# Receiver_schematic.net
KiCad netlist of a schematic drawn in EasyEDA
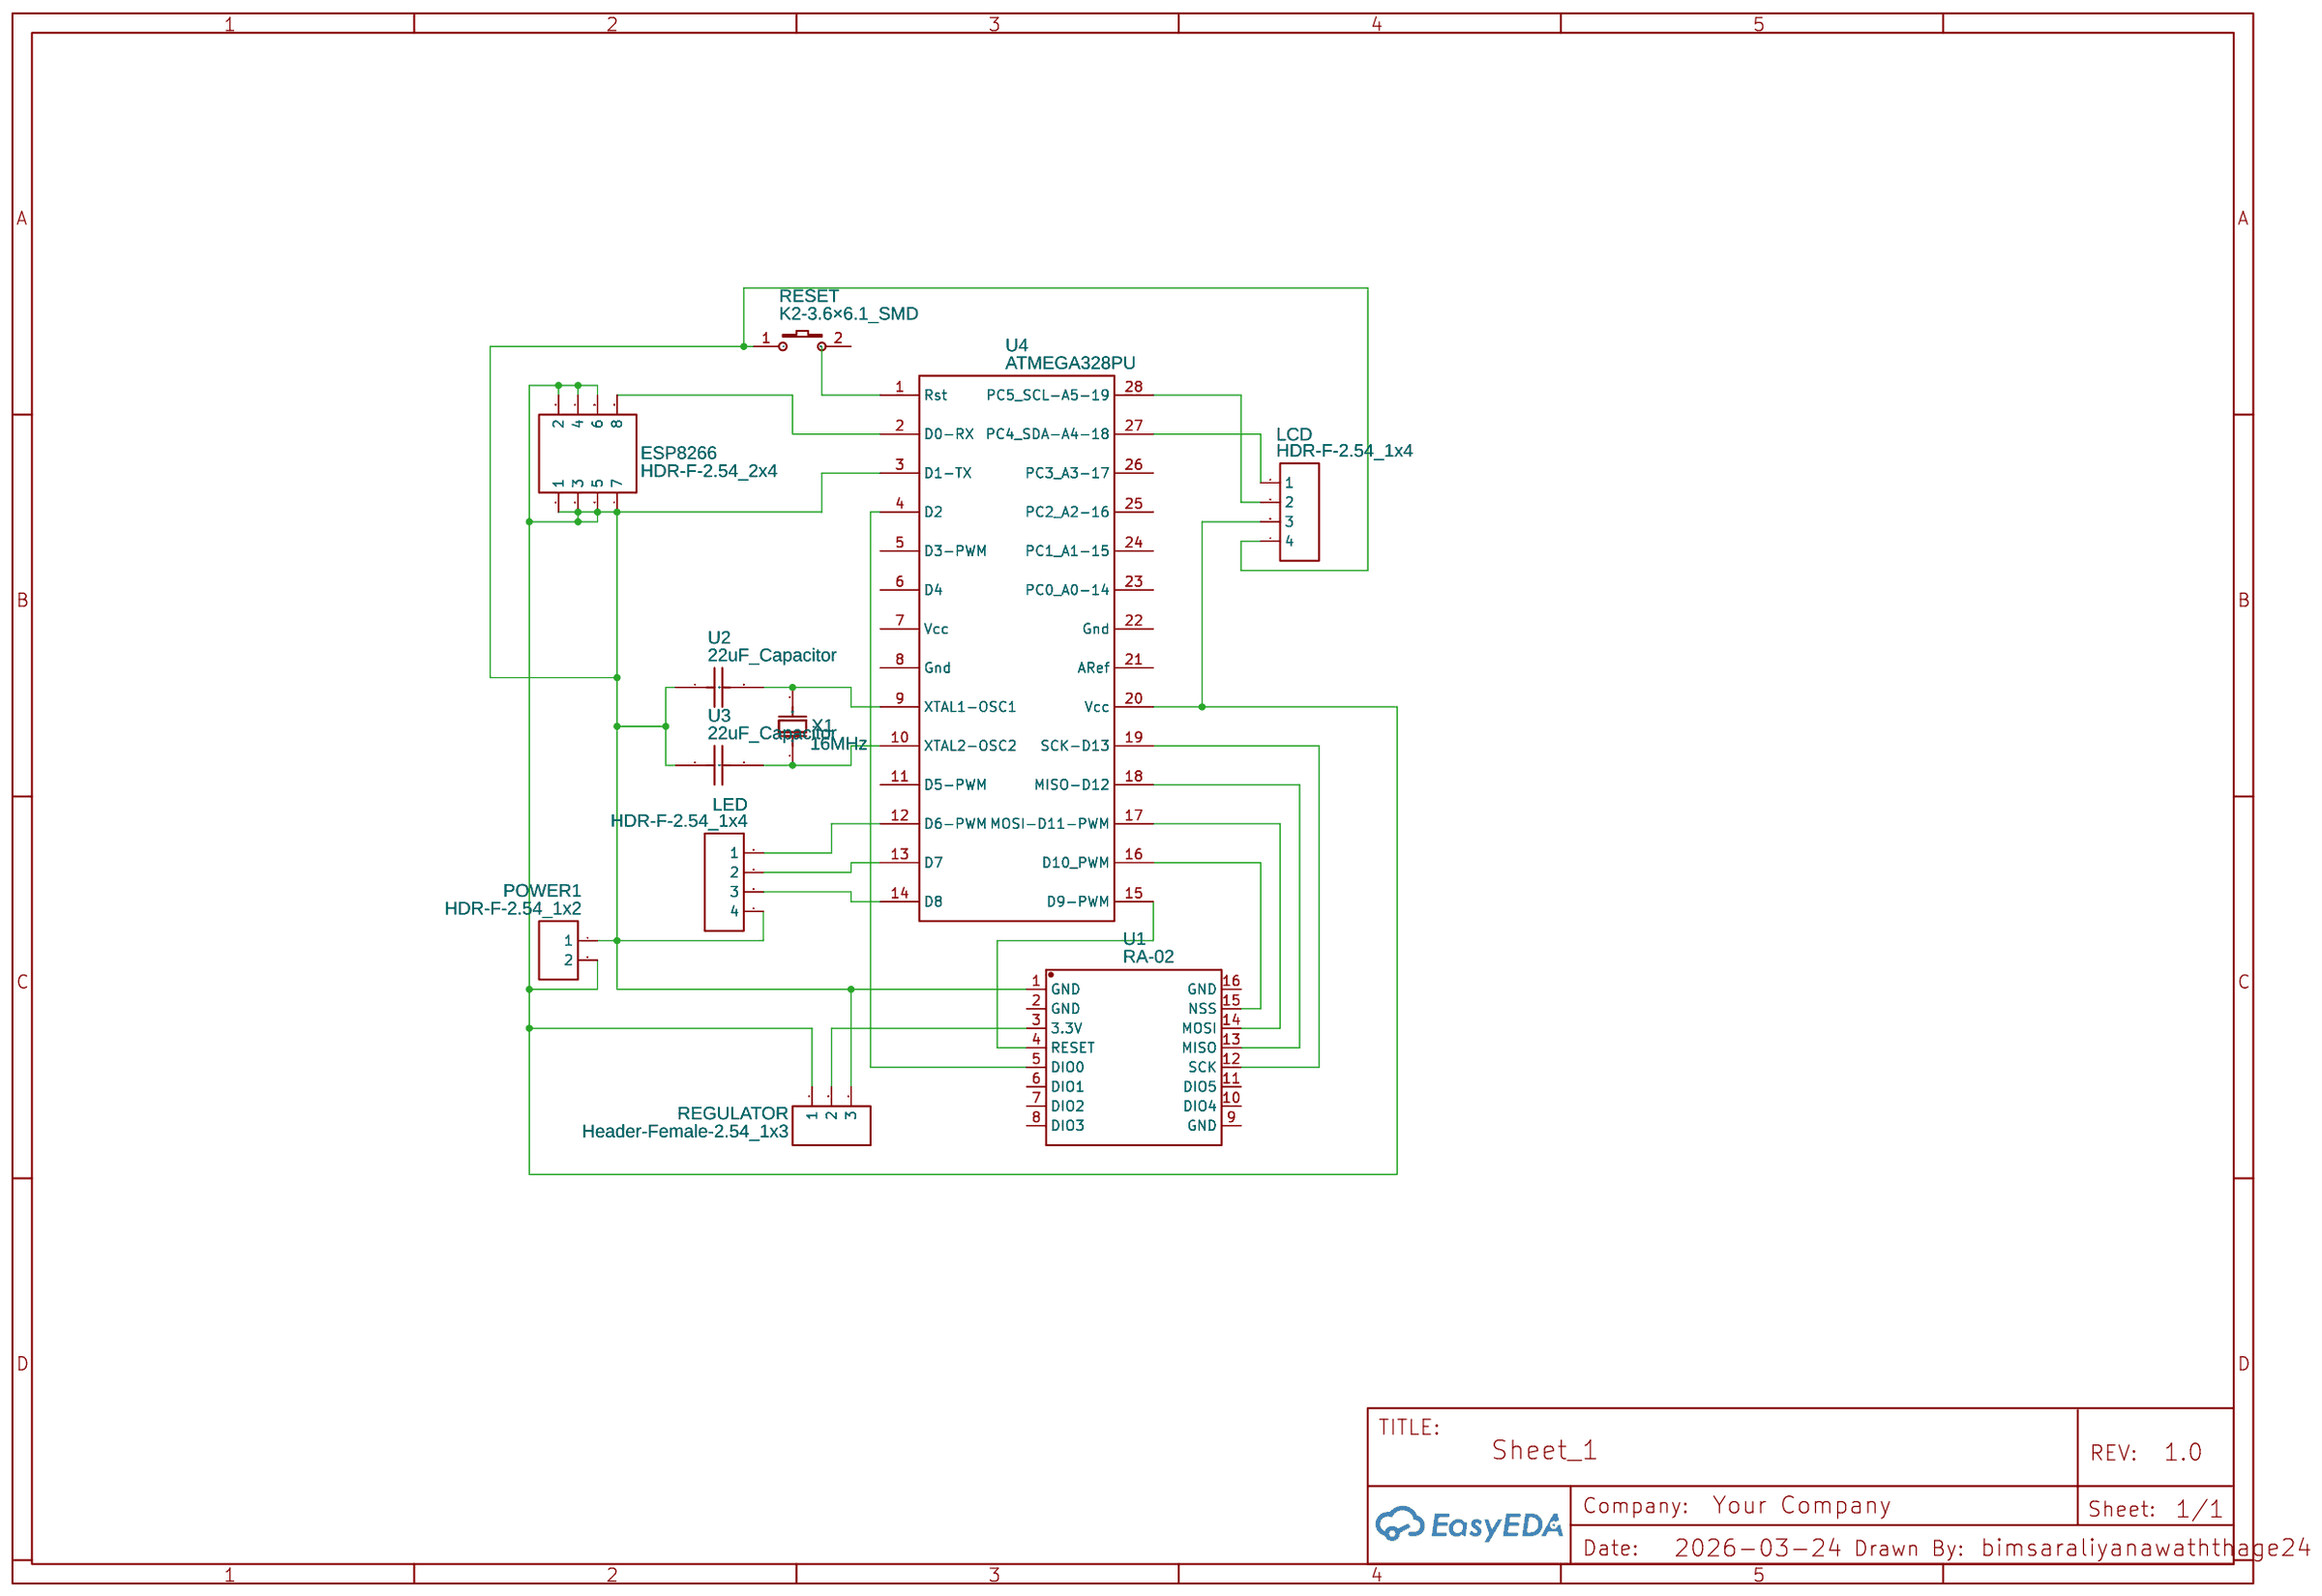
[diagram p0: schematic sheet]

(export (version "E")
  (design (tool "Eeschema 10.0.6"))
  (components
    (comp (ref "ESP8266") (value "HDR-F-2.54_2x4") (libsource (lib "") (part "HDR-F-2.54_2x4")))
    (comp (ref "LCD") (value "HDR-F-2.54_1x4") (libsource (lib "") (part "HDR-F-2.54_1x4_1")))
    (comp (ref "LED") (value "HDR-F-2.54_1x4") (libsource (lib "") (part "HDR-F-2.54_1x4")))
    (comp (ref "POWER1") (value "HDR-F-2.54_1x2") (libsource (lib "") (part "HDR-F-2.54_1x2")))
    (comp (ref "REGULATOR")
      (value "Header-Female-2.54_1x3")
      (fields (field (name "Manufacturer Part") "2.54-1*3P母") (field (name "Manufacturer") "BOOMELE(博穆精密)"))
      (libsource (lib "") (part "Header-Female-2.54_1x3"))
    )
    (comp (ref "RESET")
      (value "K2-3.6×6.1_SMD")
      (fields (field (name "Manufacturer Part") "K2-1107ST-A4SW-06"))
      (libsource (lib "") (part "K2-3.6×6.1_SMD"))
    )
    (comp (ref "U1")
      (value "RA-02")
      (fields (field (name "Manufacturer Part") "Ra-02") (field (name "Manufacturer") "Ai-Thinker(安信可)"))
      (libsource (lib "") (part "RA-02"))
    )
    (comp (ref "U2") (value "22uF_Capacitor") (libsource (lib "") (part "22uF_Capacitor")))
    (comp (ref "U3") (value "22uF_Capacitor") (libsource (lib "") (part "22uF_Capacitor")))
    (comp (ref "U4") (value "ATMEGA328PU") (libsource (lib "") (part "ATMEGA328PU")))
    (comp (ref "X1")
      (value "16MHz")
      (fields (field (name "Manufacturer Part") "9B-48.000MAAE-B") (field (name "Manufacturer") "TXC"))
      (libsource (lib "") (part "CRISTAL_16MHZ"))
    )
  )
  (nets
    (net (code "1") (name "Net-(U1-3.3V)") (class "Default")
      (node (ref "REGULATOR") (pin "2") (pinfunction "2_2") (pintype "input"))
      (node (ref "U1") (pin "3") (pinfunction "3.3V_3") (pintype "unspecified"))
    )
    (net (code "2") (name "Net-(U1-DIO0)") (class "Default")
      (node (ref "U1") (pin "5") (pinfunction "DIO0_5") (pintype "unspecified"))
      (node (ref "U4") (pin "4") (pinfunction "D2_4") (pintype "unspecified"))
    )
    (net (code "3") (name "Net-(U1-MISO)") (class "Default")
      (node (ref "U1") (pin "13") (pinfunction "MISO_13") (pintype "unspecified"))
      (node (ref "U4") (pin "18") (pinfunction "MISO-D12_18") (pintype "unspecified"))
    )
    (net (code "4") (name "Net-(U1-MOSI)") (class "Default")
      (node (ref "U1") (pin "14") (pinfunction "MOSI_14") (pintype "unspecified"))
      (node (ref "U4") (pin "17") (pinfunction "MOSI-D11-PWM_17") (pintype "unspecified"))
    )
    (net (code "5") (name "Net-(U1-NSS)") (class "Default")
      (node (ref "U1") (pin "15") (pinfunction "NSS_15") (pintype "unspecified"))
      (node (ref "U4") (pin "16") (pinfunction "D10_PWM_16") (pintype "unspecified"))
    )
    (net (code "6") (name "Net-(U1-RESET)") (class "Default")
      (node (ref "U1") (pin "4") (pinfunction "RESET_4") (pintype "unspecified"))
      (node (ref "U4") (pin "15") (pinfunction "D9-PWM_15") (pintype "unspecified"))
    )
    (net (code "7") (name "Net-(U1-SCK)") (class "Default")
      (node (ref "U1") (pin "12") (pinfunction "SCK_12") (pintype "unspecified"))
      (node (ref "U4") (pin "19") (pinfunction "SCK-D13_19") (pintype "unspecified"))
    )
    (net (code "8") (name "Net-(U4-D0-RX)") (class "Default")
      (node (ref "ESP8266") (pin "8") (pinfunction "8_8") (pintype "unspecified"))
      (node (ref "U4") (pin "2") (pinfunction "D0-RX_2") (pintype "unspecified"))
    )
    (net (code "9") (name "Net-(U4-D1-TX)") (class "Default")
      (node (ref "ESP8266") (pin "1") (pinfunction "1_1") (pintype "unspecified"))
      (node (ref "ESP8266") (pin "2") (pinfunction "2_2") (pintype "unspecified"))
      (node (ref "ESP8266") (pin "3") (pinfunction "3_3") (pintype "unspecified"))
      (node (ref "ESP8266") (pin "4") (pinfunction "4_4") (pintype "unspecified"))
      (node (ref "ESP8266") (pin "5") (pinfunction "5_5") (pintype "unspecified"))
      (node (ref "ESP8266") (pin "6") (pinfunction "6_6") (pintype "unspecified"))
      (node (ref "ESP8266") (pin "7") (pinfunction "7_7") (pintype "unspecified"))
      (node (ref "LCD") (pin "3") (pinfunction "3_3") (pintype "unspecified"))
      (node (ref "LCD") (pin "4") (pinfunction "4_4") (pintype "unspecified"))
      (node (ref "LED") (pin "4") (pinfunction "4_4") (pintype "unspecified"))
      (node (ref "POWER1") (pin "1") (pinfunction "1_1") (pintype "input"))
      (node (ref "POWER1") (pin "2") (pinfunction "2_2") (pintype "input"))
      (node (ref "REGULATOR") (pin "1") (pinfunction "1_1") (pintype "input"))
      (node (ref "REGULATOR") (pin "3") (pinfunction "3_3") (pintype "input"))
      (node (ref "RESET") (pin "1") (pinfunction "1_1") (pintype "unspecified"))
      (node (ref "U1") (pin "1") (pinfunction "GND_1") (pintype "unspecified"))
      (node (ref "U2") (pin "1") (pinfunction "1_1") (pintype "unspecified"))
      (node (ref "U3") (pin "1") (pinfunction "1_1") (pintype "unspecified"))
      (node (ref "U4") (pin "20") (pinfunction "Vcc_20") (pintype "unspecified"))
      (node (ref "U4") (pin "3") (pinfunction "D1-TX_3") (pintype "unspecified"))
    )
    (net (code "10") (name "Net-(U4-D6-PWM)") (class "Default")
      (node (ref "LED") (pin "1") (pinfunction "1_1") (pintype "unspecified"))
      (node (ref "U4") (pin "12") (pinfunction "D6-PWM_12") (pintype "unspecified"))
    )
    (net (code "11") (name "Net-(U4-D7)") (class "Default")
      (node (ref "LED") (pin "2") (pinfunction "2_2") (pintype "unspecified"))
      (node (ref "U4") (pin "13") (pinfunction "D7_13") (pintype "unspecified"))
    )
    (net (code "12") (name "Net-(U4-D8)") (class "Default")
      (node (ref "LED") (pin "3") (pinfunction "3_3") (pintype "unspecified"))
      (node (ref "U4") (pin "14") (pinfunction "D8_14") (pintype "unspecified"))
    )
    (net (code "13") (name "Net-(U4-PC4_SDA-A4-18)") (class "Default")
      (node (ref "LCD") (pin "1") (pinfunction "1_1") (pintype "unspecified"))
      (node (ref "U4") (pin "27") (pinfunction "PC4_SDA-A4-18_27") (pintype "unspecified"))
    )
    (net (code "14") (name "Net-(U4-PC5_SCL-A5-19)") (class "Default")
      (node (ref "LCD") (pin "2") (pinfunction "2_2") (pintype "unspecified"))
      (node (ref "U4") (pin "28") (pinfunction "PC5_SCL-A5-19_28") (pintype "unspecified"))
    )
    (net (code "15") (name "Net-(U4-XTAL1-OSC1)") (class "Default")
      (node (ref "U2") (pin "2") (pinfunction "2_2") (pintype "unspecified"))
      (node (ref "U4") (pin "9") (pinfunction "XTAL1-OSC1_9") (pintype "unspecified"))
      (node (ref "X1") (pin "2") (pinfunction "OSC2_2") (pintype "unspecified"))
    )
    (net (code "16") (name "Net-(U4-XTAL2-OSC2)") (class "Default")
      (node (ref "U3") (pin "2") (pinfunction "2_2") (pintype "unspecified"))
      (node (ref "U4") (pin "10") (pinfunction "XTAL2-OSC2_10") (pintype "unspecified"))
      (node (ref "X1") (pin "1") (pinfunction "OSC1_1") (pintype "unspecified"))
    )
    (net (code "17") (name "unconnected-(RESET-Pad2)") (class "Default")
      (node (ref "RESET") (pin "2") (pinfunction "2_2") (pintype "unspecified"))
    )
    (net (code "18") (name "unconnected-(U1-DIO1-Pad6)") (class "Default")
      (node (ref "U1") (pin "6") (pinfunction "DIO1_6") (pintype "unspecified"))
    )
    (net (code "19") (name "unconnected-(U1-DIO2-Pad7)") (class "Default")
      (node (ref "U1") (pin "7") (pinfunction "DIO2_7") (pintype "unspecified"))
    )
    (net (code "20") (name "unconnected-(U1-DIO3-Pad8)") (class "Default")
      (node (ref "U1") (pin "8") (pinfunction "DIO3_8") (pintype "unspecified"))
    )
    (net (code "21") (name "unconnected-(U1-DIO4-Pad10)") (class "Default")
      (node (ref "U1") (pin "10") (pinfunction "DIO4_10") (pintype "unspecified"))
    )
    (net (code "22") (name "unconnected-(U1-DIO5-Pad11)") (class "Default")
      (node (ref "U1") (pin "11") (pinfunction "DIO5_11") (pintype "unspecified"))
    )
    (net (code "23") (name "unconnected-(U1-GND-Pad2)") (class "Default")
      (node (ref "U1") (pin "2") (pinfunction "GND_2") (pintype "unspecified"))
    )
    (net (code "24") (name "unconnected-(U1-GND-Pad9)") (class "Default")
      (node (ref "U1") (pin "9") (pinfunction "GND_9") (pintype "unspecified"))
    )
    (net (code "25") (name "unconnected-(U1-GND-Pad16)") (class "Default")
      (node (ref "U1") (pin "16") (pinfunction "GND_16") (pintype "unspecified"))
    )
    (net (code "26") (name "unconnected-(U4-ARef-Pad21)") (class "Default")
      (node (ref "U4") (pin "21") (pinfunction "ARef_21") (pintype "unspecified"))
    )
    (net (code "27") (name "unconnected-(U4-D3-PWM-Pad5)") (class "Default")
      (node (ref "U4") (pin "5") (pinfunction "D3-PWM_5") (pintype "unspecified"))
    )
    (net (code "28") (name "unconnected-(U4-D4-Pad6)") (class "Default")
      (node (ref "U4") (pin "6") (pinfunction "D4_6") (pintype "unspecified"))
    )
    (net (code "29") (name "unconnected-(U4-D5-PWM-Pad11)") (class "Default")
      (node (ref "U4") (pin "11") (pinfunction "D5-PWM_11") (pintype "unspecified"))
    )
    (net (code "30") (name "unconnected-(U4-Gnd-Pad8)") (class "Default")
      (node (ref "U4") (pin "8") (pinfunction "Gnd_8") (pintype "unspecified"))
    )
    (net (code "31") (name "unconnected-(U4-Gnd-Pad22)") (class "Default")
      (node (ref "U4") (pin "22") (pinfunction "Gnd_22") (pintype "unspecified"))
    )
    (net (code "32") (name "unconnected-(U4-PC0_A0-14-Pad23)") (class "Default")
      (node (ref "U4") (pin "23") (pinfunction "PC0_A0-14_23") (pintype "unspecified"))
    )
    (net (code "33") (name "unconnected-(U4-PC1_A1-15-Pad24)") (class "Default")
      (node (ref "U4") (pin "24") (pinfunction "PC1_A1-15_24") (pintype "unspecified"))
    )
    (net (code "34") (name "unconnected-(U4-PC2_A2-16-Pad25)") (class "Default")
      (node (ref "U4") (pin "25") (pinfunction "PC2_A2-16_25") (pintype "unspecified"))
    )
    (net (code "35") (name "unconnected-(U4-PC3_A3-17-Pad26)") (class "Default")
      (node (ref "U4") (pin "26") (pinfunction "PC3_A3-17_26") (pintype "unspecified"))
    )
    (net (code "36") (name "unconnected-(U4-Rst-Pad1)") (class "Default")
      (node (ref "U4") (pin "1") (pinfunction "Rst_1") (pintype "unspecified"))
    )
    (net (code "37") (name "unconnected-(U4-Vcc-Pad7)") (class "Default")
      (node (ref "U4") (pin "7") (pinfunction "Vcc_7") (pintype "unspecified"))
    )
  )
)
